# DIP16-2-2_54.net
KiCad netlist of a schematic drawn in EAGLE
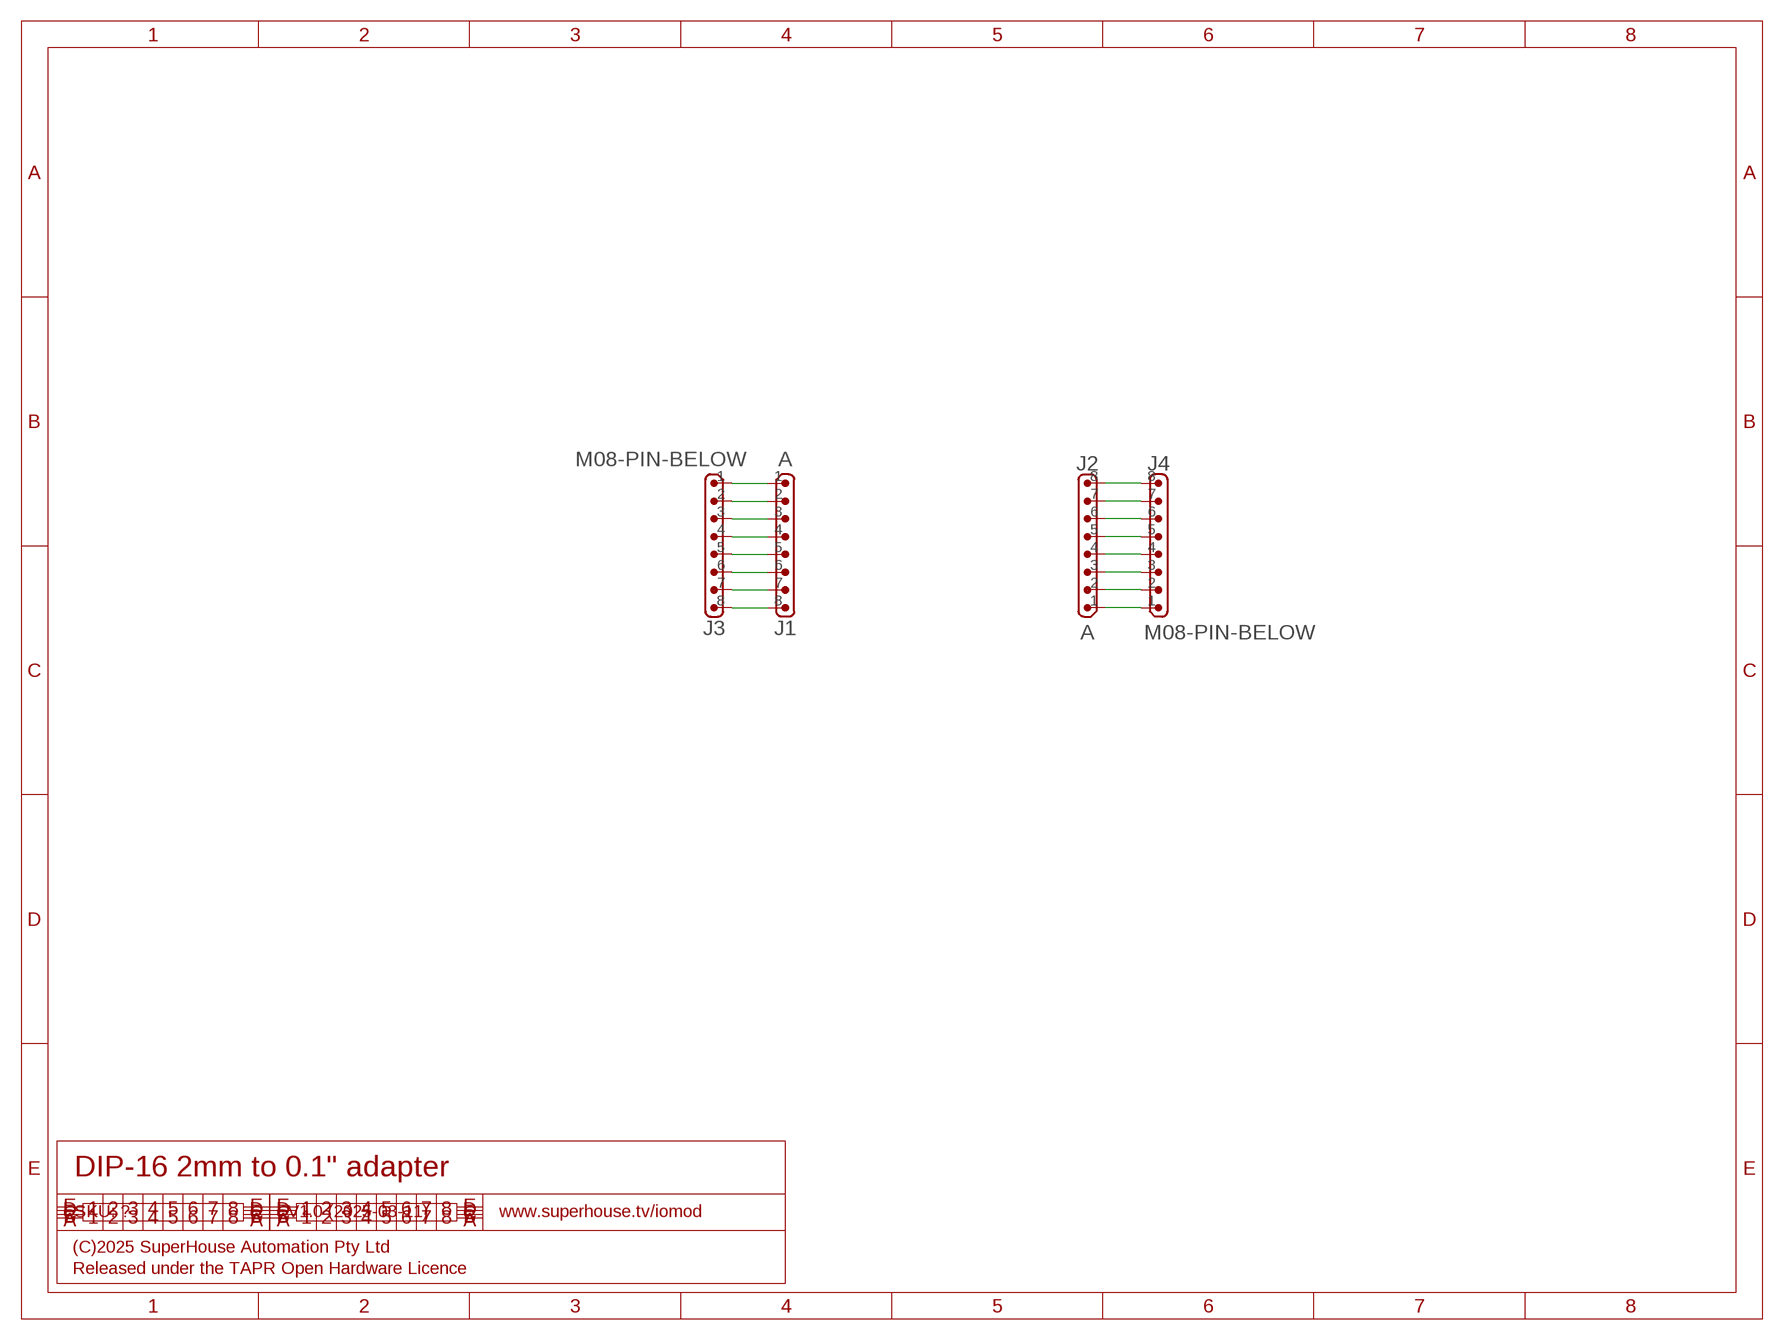
[diagram p0: schematic, sheet 1]

(export (version "E")
  (design (tool "Eeschema 10.0.6"))
  (components
    (comp (ref "J1")
      (value "A")
      (footprint "eagle-import:1X8-2.00-S")
      (libsource (lib "eagle-import") (part "M08-2.00-S"))
    )
    (comp (ref "J2")
      (value "A")
      (footprint "eagle-import:1X8-2.00-S")
      (libsource (lib "eagle-import") (part "M08-2.00-S"))
    )
    (comp (ref "J3")
      (value "M08-PIN-BELOW")
      (footprint "eagle-import:1X08-P-BELOW")
      (libsource (lib "eagle-import") (part "M08-PIN-BELOW"))
    )
    (comp (ref "J4")
      (value "M08-PIN-BELOW")
      (footprint "eagle-import:1X08-P-BELOW")
      (libsource (lib "eagle-import") (part "M08-PIN-BELOW"))
    )
  )
  (nets
    (net (code "1") (name "Net-(J1-Pad1)") (class "Default")
      (node (ref "J1") (pin "1") (pinfunction "1_1") (pintype "passive"))
      (node (ref "J3") (pin "1") (pinfunction "1_1") (pintype "passive"))
    )
    (net (code "2") (name "Net-(J1-Pad2)") (class "Default")
      (node (ref "J1") (pin "2") (pinfunction "2_2") (pintype "passive"))
      (node (ref "J3") (pin "2") (pinfunction "2_2") (pintype "passive"))
    )
    (net (code "3") (name "Net-(J1-Pad3)") (class "Default")
      (node (ref "J1") (pin "3") (pinfunction "3_3") (pintype "passive"))
      (node (ref "J3") (pin "3") (pinfunction "3_3") (pintype "passive"))
    )
    (net (code "4") (name "Net-(J1-Pad4)") (class "Default")
      (node (ref "J1") (pin "4") (pinfunction "4_4") (pintype "passive"))
      (node (ref "J3") (pin "4") (pinfunction "4_4") (pintype "passive"))
    )
    (net (code "5") (name "Net-(J1-Pad5)") (class "Default")
      (node (ref "J1") (pin "5") (pinfunction "5_5") (pintype "passive"))
      (node (ref "J3") (pin "5") (pinfunction "5_5") (pintype "passive"))
    )
    (net (code "6") (name "Net-(J1-Pad6)") (class "Default")
      (node (ref "J1") (pin "6") (pinfunction "6_6") (pintype "passive"))
      (node (ref "J3") (pin "6") (pinfunction "6_6") (pintype "passive"))
    )
    (net (code "7") (name "Net-(J1-Pad7)") (class "Default")
      (node (ref "J1") (pin "7") (pinfunction "7_7") (pintype "passive"))
      (node (ref "J3") (pin "7") (pinfunction "7_7") (pintype "passive"))
    )
    (net (code "8") (name "Net-(J1-Pad8)") (class "Default")
      (node (ref "J1") (pin "8") (pinfunction "8_8") (pintype "passive"))
      (node (ref "J3") (pin "8") (pinfunction "8_8") (pintype "passive"))
    )
    (net (code "9") (name "Net-(J2-Pad1)") (class "Default")
      (node (ref "J2") (pin "1") (pinfunction "1_1") (pintype "passive"))
      (node (ref "J4") (pin "1") (pinfunction "1_1") (pintype "passive"))
    )
    (net (code "10") (name "Net-(J2-Pad2)") (class "Default")
      (node (ref "J2") (pin "2") (pinfunction "2_2") (pintype "passive"))
      (node (ref "J4") (pin "2") (pinfunction "2_2") (pintype "passive"))
    )
    (net (code "11") (name "Net-(J2-Pad3)") (class "Default")
      (node (ref "J2") (pin "3") (pinfunction "3_3") (pintype "passive"))
      (node (ref "J4") (pin "3") (pinfunction "3_3") (pintype "passive"))
    )
    (net (code "12") (name "Net-(J2-Pad4)") (class "Default")
      (node (ref "J2") (pin "4") (pinfunction "4_4") (pintype "passive"))
      (node (ref "J4") (pin "4") (pinfunction "4_4") (pintype "passive"))
    )
    (net (code "13") (name "Net-(J2-Pad5)") (class "Default")
      (node (ref "J2") (pin "5") (pinfunction "5_5") (pintype "passive"))
      (node (ref "J4") (pin "5") (pinfunction "5_5") (pintype "passive"))
    )
    (net (code "14") (name "Net-(J2-Pad6)") (class "Default")
      (node (ref "J2") (pin "6") (pinfunction "6_6") (pintype "passive"))
      (node (ref "J4") (pin "6") (pinfunction "6_6") (pintype "passive"))
    )
    (net (code "15") (name "Net-(J2-Pad7)") (class "Default")
      (node (ref "J2") (pin "7") (pinfunction "7_7") (pintype "passive"))
      (node (ref "J4") (pin "7") (pinfunction "7_7") (pintype "passive"))
    )
    (net (code "16") (name "Net-(J2-Pad8)") (class "Default")
      (node (ref "J2") (pin "8") (pinfunction "8_8") (pintype "passive"))
      (node (ref "J4") (pin "8") (pinfunction "8_8") (pintype "passive"))
    )
  )
)
